# MPU-6050_BreakoutV11.net
KiCad netlist of a schematic drawn in EAGLE
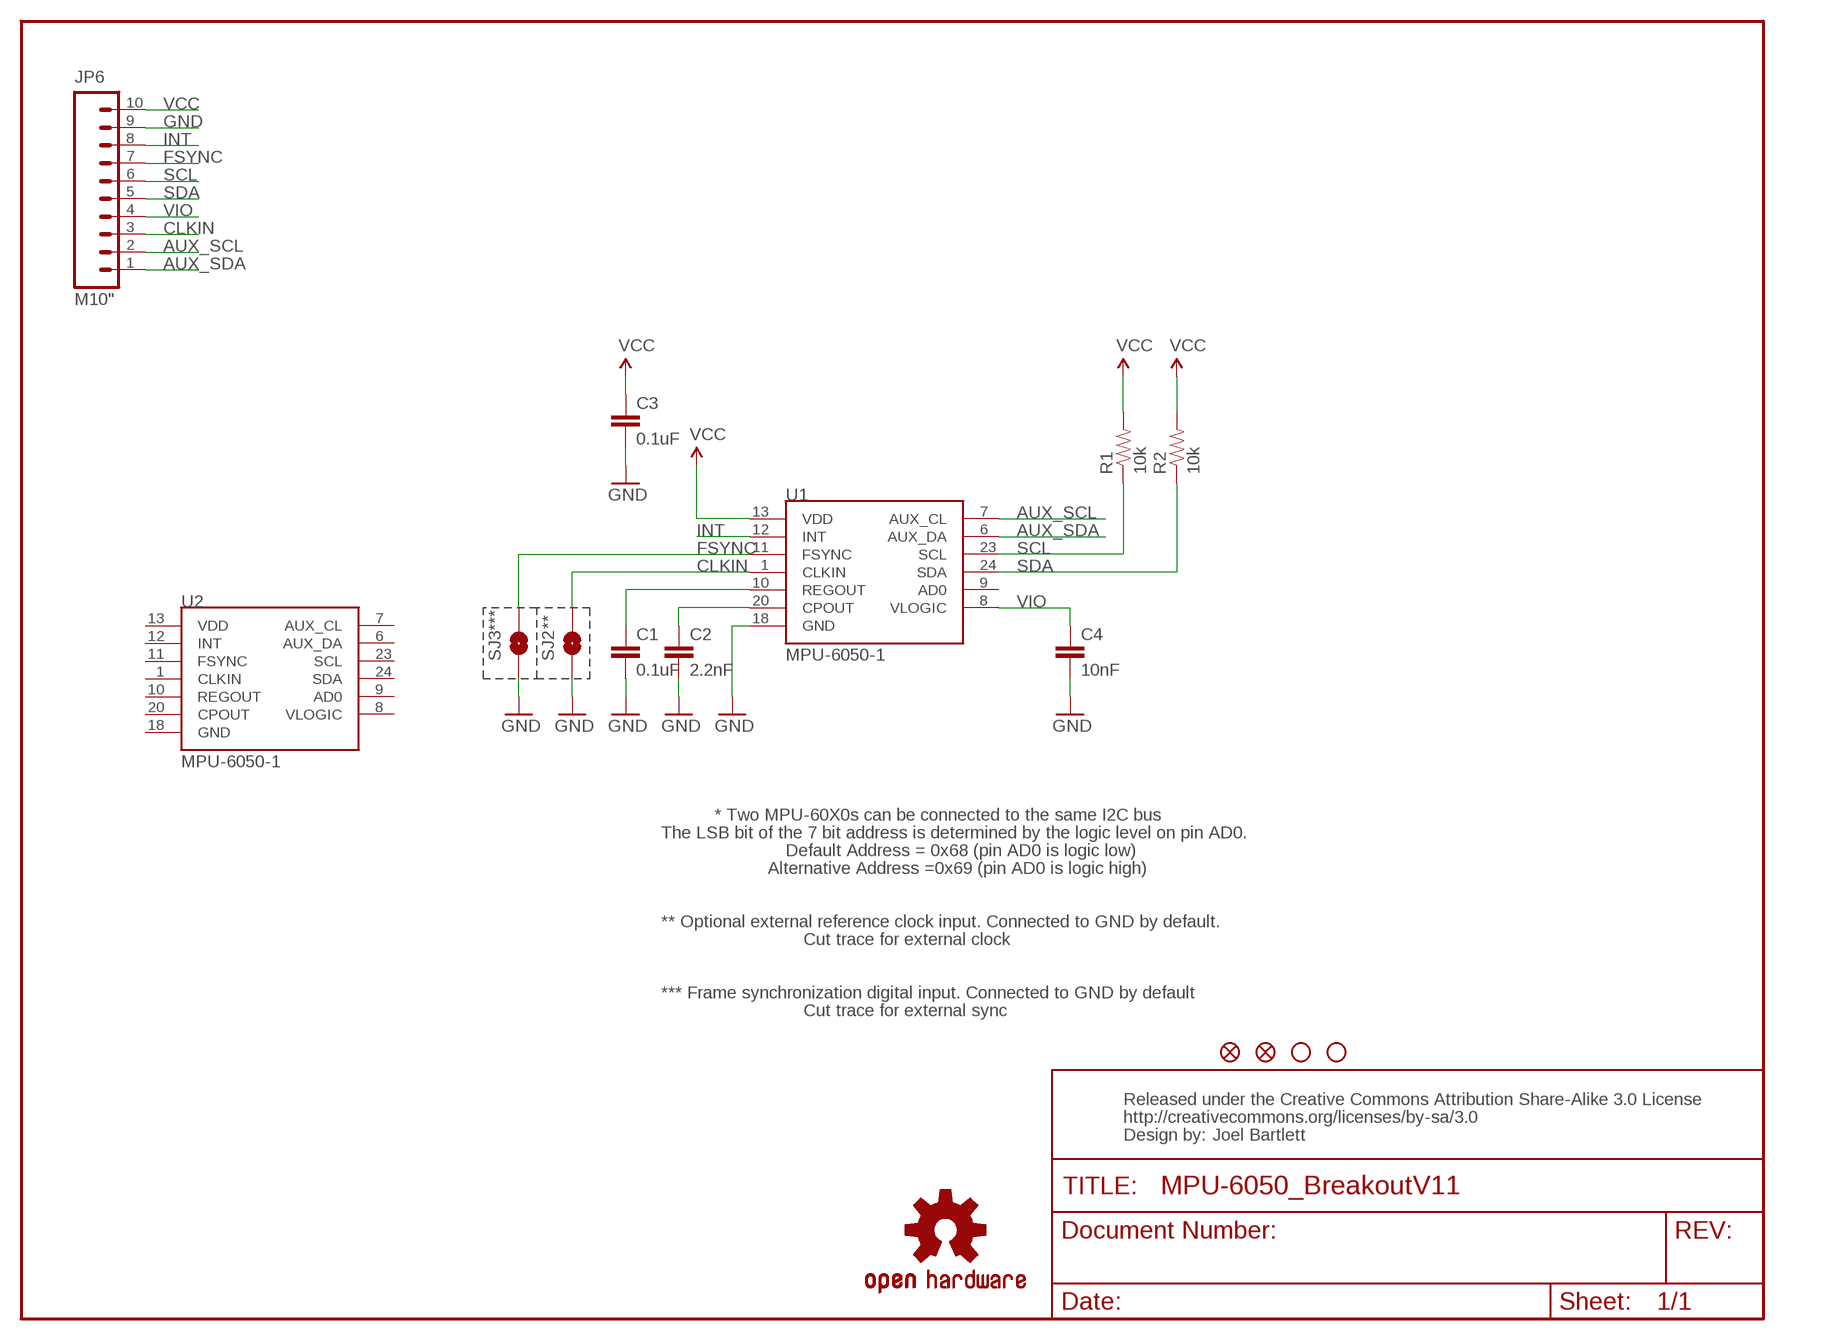
[diagram p0: schematic, sheet 1]

(export (version "E")
  (design (tool "Eeschema 10.0.6"))
  (components
    (comp (ref "C1")
      (value "0.1uF")
      (footprint "eagle-import:0402-CAP")
      (libsource (lib "eagle-import") (part "CAP0402-CAP"))
    )
    (comp (ref "C2")
      (value "2.2nF")
      (footprint "eagle-import:0402-CAP")
      (libsource (lib "eagle-import") (part "CAP0402-CAP"))
    )
    (comp (ref "C3")
      (value "0.1uF")
      (footprint "eagle-import:0402-CAP")
      (libsource (lib "eagle-import") (part "CAP0402-CAP"))
    )
    (comp (ref "C4")
      (value "10nF")
      (footprint "eagle-import:0402-CAP")
      (libsource (lib "eagle-import") (part "CAP0402-CAP"))
    )
    (comp (ref "JP2")
      (value "FIDUCIALUFIDUCIAL")
      (footprint "eagle-import:MICRO-FIDUCIAL")
      (libsource (lib "eagle-import") (part "FIDUCIALUFIDUCIAL"))
    )
    (comp (ref "JP3")
      (value "STAND-OFFTIGHT")
      (footprint "eagle-import:STAND-OFF-TIGHT")
      (libsource (lib "eagle-import") (part "STAND-OFFTIGHT"))
    )
    (comp (ref "JP4")
      (value "STAND-OFFTIGHT")
      (footprint "eagle-import:STAND-OFF-TIGHT")
      (libsource (lib "eagle-import") (part "STAND-OFFTIGHT"))
    )
    (comp (ref "JP5")
      (value "FIDUCIALUFIDUCIAL")
      (footprint "eagle-import:MICRO-FIDUCIAL")
      (libsource (lib "eagle-import") (part "FIDUCIALUFIDUCIAL"))
    )
    (comp (ref "JP6")
      (value "M10\"")
      (footprint "eagle-import:1X10")
      (libsource (lib "eagle-import") (part "M10{dblquote}"))
    )
    (comp (ref "R1")
      (value "10k")
      (footprint "eagle-import:0402-RES")
      (libsource (lib "eagle-import") (part "RESISTOR0402-RES"))
    )
    (comp (ref "R2")
      (value "10k")
      (footprint "eagle-import:0402-RES")
      (libsource (lib "eagle-import") (part "RESISTOR0402-RES"))
    )
    (comp (ref "SJ2")
      (value "SOLDERJUMPERTRACE")
      (footprint "eagle-import:SJ_2S-TRACE")
      (libsource (lib "eagle-import") (part "SOLDERJUMPERTRACE"))
    )
    (comp (ref "SJ3")
      (value "SOLDERJUMPERTRACE")
      (footprint "eagle-import:SJ_2S-TRACE")
      (libsource (lib "eagle-import") (part "SOLDERJUMPERTRACE"))
    )
    (comp (ref "U$1")
      (value "OSHW-LOGOS")
      (footprint "eagle-import:OSHW-LOGO-S")
      (libsource (lib "eagle-import") (part "OSHW-LOGOS"))
    )
    (comp (ref "U1")
      (value "MPU-6050-1")
      (footprint "eagle-import:QFN-24-4MM2")
      (libsource (lib "eagle-import") (part "MPU-6050-1"))
    )
    (comp (ref "U2")
      (value "MPU-6050-1")
      (footprint "eagle-import:QFN-24-4MM2")
      (libsource (lib "eagle-import") (part "MPU-6050-1"))
    )
    (comp (ref "U3")
      (value "CREATIVE_COMMONS")
      (footprint "eagle-import:CREATIVE_COMMONS")
      (libsource (lib "eagle-import") (part "CREATIVE_COMMONS"))
    )
  )
  (nets
    (net (code "1") (name "/AUX_SCL") (class "Default")
      (node (ref "JP6") (pin "2") (pinfunction "2_2") (pintype "passive"))
      (node (ref "U1") (pin "7") (pinfunction "AUX_CL_7") (pintype "bidirectional"))
    )
    (net (code "2") (name "/AUX_SDA") (class "Default")
      (node (ref "JP6") (pin "1") (pinfunction "1_1") (pintype "passive"))
      (node (ref "U1") (pin "6") (pinfunction "AUX_DA_6") (pintype "bidirectional"))
    )
    (net (code "3") (name "/CLKIN") (class "Default")
      (node (ref "JP6") (pin "3") (pinfunction "3_3") (pintype "passive"))
      (node (ref "SJ2") (pin "2") (pinfunction "2_2") (pintype "passive"))
      (node (ref "U1") (pin "1") (pinfunction "CLKIN_1") (pintype "bidirectional"))
    )
    (net (code "4") (name "/FSYNC") (class "Default")
      (node (ref "JP6") (pin "7") (pinfunction "7_7") (pintype "passive"))
      (node (ref "SJ3") (pin "2") (pinfunction "2_2") (pintype "passive"))
      (node (ref "U1") (pin "11") (pinfunction "FSYNC_11") (pintype "bidirectional"))
    )
    (net (code "5") (name "/INT") (class "Default")
      (node (ref "JP6") (pin "8") (pinfunction "8_8") (pintype "passive"))
      (node (ref "U1") (pin "12") (pinfunction "INT_12") (pintype "bidirectional"))
    )
    (net (code "6") (name "/SCL") (class "Default")
      (node (ref "JP6") (pin "6") (pinfunction "6_6") (pintype "passive"))
      (node (ref "R1") (pin "1") (pinfunction "1_1") (pintype "passive"))
      (node (ref "U1") (pin "23") (pinfunction "SCL_23") (pintype "bidirectional"))
    )
    (net (code "7") (name "/SDA") (class "Default")
      (node (ref "JP6") (pin "5") (pinfunction "5_5") (pintype "passive"))
      (node (ref "R2") (pin "1") (pinfunction "1_1") (pintype "passive"))
      (node (ref "U1") (pin "24") (pinfunction "SDA_24") (pintype "bidirectional"))
    )
    (net (code "8") (name "/VIO") (class "Default")
      (node (ref "C4") (pin "1") (pinfunction "1_1") (pintype "passive"))
      (node (ref "JP6") (pin "4") (pinfunction "4_4") (pintype "passive"))
      (node (ref "U1") (pin "8") (pinfunction "VLOGIC_8") (pintype "bidirectional"))
    )
    (net (code "9") (name "GND") (class "Default")
      (node (ref "C1") (pin "2") (pinfunction "2_2") (pintype "passive"))
      (node (ref "C2") (pin "2") (pinfunction "2_2") (pintype "passive"))
      (node (ref "C3") (pin "2") (pinfunction "2_2") (pintype "passive"))
      (node (ref "C4") (pin "2") (pinfunction "2_2") (pintype "passive"))
      (node (ref "JP6") (pin "9") (pinfunction "9_9") (pintype "passive"))
      (node (ref "SJ2") (pin "1") (pinfunction "1_1") (pintype "passive"))
      (node (ref "SJ3") (pin "1") (pinfunction "1_1") (pintype "passive"))
      (node (ref "U1") (pin "18") (pinfunction "GND_18") (pintype "bidirectional"))
    )
    (net (code "10") (name "Net-(U1-CPOUT)") (class "Default")
      (node (ref "C2") (pin "1") (pinfunction "1_1") (pintype "passive"))
      (node (ref "U1") (pin "20") (pinfunction "CPOUT_20") (pintype "bidirectional"))
    )
    (net (code "11") (name "Net-(U1-REGOUT)") (class "Default")
      (node (ref "C1") (pin "1") (pinfunction "1_1") (pintype "passive"))
      (node (ref "U1") (pin "10") (pinfunction "REGOUT_10") (pintype "bidirectional"))
    )
    (net (code "12") (name "VCC") (class "Default")
      (node (ref "C3") (pin "1") (pinfunction "1_1") (pintype "passive"))
      (node (ref "JP6") (pin "10") (pinfunction "10_10") (pintype "passive"))
      (node (ref "R1") (pin "2") (pinfunction "2_2") (pintype "passive"))
      (node (ref "R2") (pin "2") (pinfunction "2_2") (pintype "passive"))
      (node (ref "U1") (pin "13") (pinfunction "VDD_13") (pintype "bidirectional"))
    )
    (net (code "13") (name "unconnected-(U1-AD0-Pad9)") (class "Default")
      (node (ref "U1") (pin "9") (pinfunction "AD0_9") (pintype "bidirectional"))
    )
    (net (code "14") (name "unconnected-(U2-AD0-Pad9)") (class "Default")
      (node (ref "U2") (pin "9") (pinfunction "AD0_9") (pintype "bidirectional"))
    )
    (net (code "15") (name "unconnected-(U2-AUX_CL-Pad7)") (class "Default")
      (node (ref "U2") (pin "7") (pinfunction "AUX_CL_7") (pintype "bidirectional"))
    )
    (net (code "16") (name "unconnected-(U2-AUX_DA-Pad6)") (class "Default")
      (node (ref "U2") (pin "6") (pinfunction "AUX_DA_6") (pintype "bidirectional"))
    )
    (net (code "17") (name "unconnected-(U2-CLKIN-Pad1)") (class "Default")
      (node (ref "U2") (pin "1") (pinfunction "CLKIN_1") (pintype "bidirectional"))
    )
    (net (code "18") (name "unconnected-(U2-CPOUT-Pad20)") (class "Default")
      (node (ref "U2") (pin "20") (pinfunction "CPOUT_20") (pintype "bidirectional"))
    )
    (net (code "19") (name "unconnected-(U2-FSYNC-Pad11)") (class "Default")
      (node (ref "U2") (pin "11") (pinfunction "FSYNC_11") (pintype "bidirectional"))
    )
    (net (code "20") (name "unconnected-(U2-GND-Pad18)") (class "Default")
      (node (ref "U2") (pin "18") (pinfunction "GND_18") (pintype "bidirectional"))
    )
    (net (code "21") (name "unconnected-(U2-INT-Pad12)") (class "Default")
      (node (ref "U2") (pin "12") (pinfunction "INT_12") (pintype "bidirectional"))
    )
    (net (code "22") (name "unconnected-(U2-REGOUT-Pad10)") (class "Default")
      (node (ref "U2") (pin "10") (pinfunction "REGOUT_10") (pintype "bidirectional"))
    )
    (net (code "23") (name "unconnected-(U2-SCL-Pad23)") (class "Default")
      (node (ref "U2") (pin "23") (pinfunction "SCL_23") (pintype "bidirectional"))
    )
    (net (code "24") (name "unconnected-(U2-SDA-Pad24)") (class "Default")
      (node (ref "U2") (pin "24") (pinfunction "SDA_24") (pintype "bidirectional"))
    )
    (net (code "25") (name "unconnected-(U2-VDD-Pad13)") (class "Default")
      (node (ref "U2") (pin "13") (pinfunction "VDD_13") (pintype "bidirectional"))
    )
    (net (code "26") (name "unconnected-(U2-VLOGIC-Pad8)") (class "Default")
      (node (ref "U2") (pin "8") (pinfunction "VLOGIC_8") (pintype "bidirectional"))
    )
  )
)
